# RC_shield.net
KiCad netlist of a schematic drawn in EAGLE
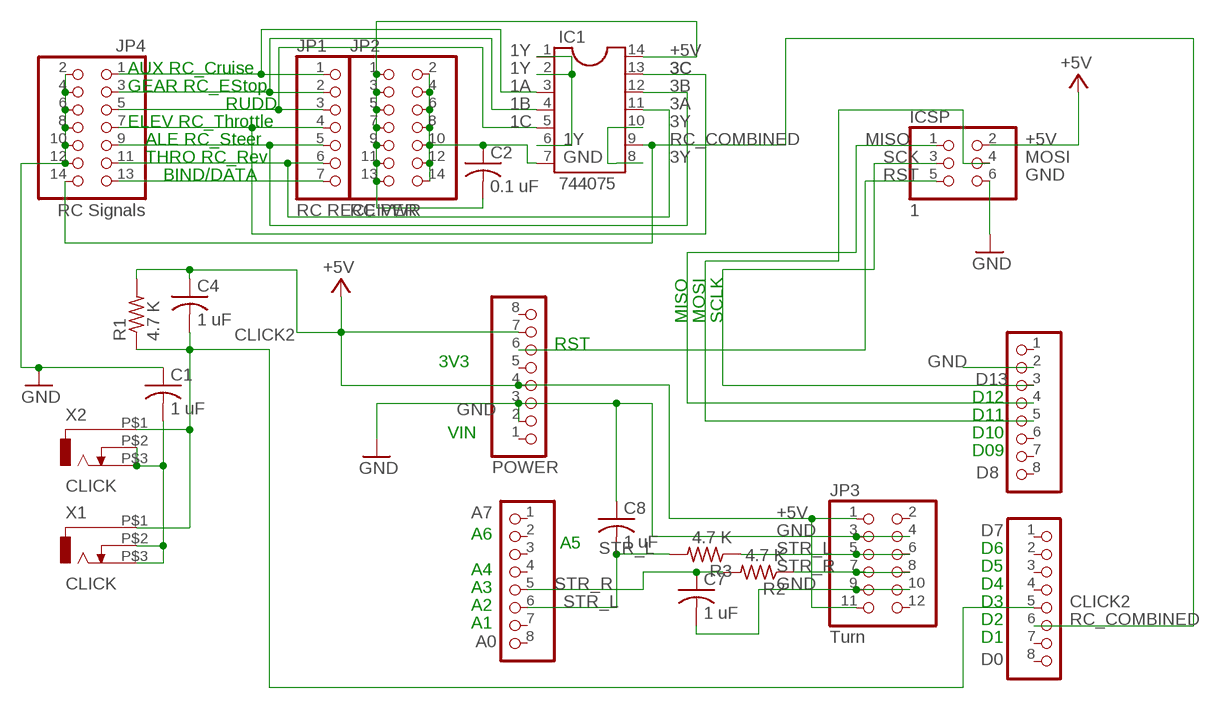
[diagram p0: schematic, sheet 1]

(export (version "E")
  (design (tool "Eeschema 10.0.6"))
  (components
    (comp (ref "A0")
      (value "A7")
      (footprint "eagle-import:1X08")
      (libsource (lib "eagle-import") (part "PINHD-1X8"))
    )
    (comp (ref "C1")
      (value "1 uF")
      (footprint "eagle-import:C025-030X050")
      (libsource (lib "eagle-import") (part "C-US025-030X050"))
    )
    (comp (ref "C2")
      (value "0.1 uF")
      (footprint "eagle-import:C025-030X050")
      (libsource (lib "eagle-import") (part "C-US025-030X050"))
    )
    (comp (ref "C4")
      (value "1 uF")
      (footprint "eagle-import:C025-030X050")
      (libsource (lib "eagle-import") (part "C-US025-030X050"))
    )
    (comp (ref "C7")
      (value "1 uF")
      (footprint "eagle-import:C025-030X050")
      (libsource (lib "eagle-import") (part "C-US025-030X050"))
    )
    (comp (ref "C8")
      (value "1 uF")
      (footprint "eagle-import:C025-030X050")
      (libsource (lib "eagle-import") (part "C-US025-030X050"))
    )
    (comp (ref "D0")
      (value "D7")
      (footprint "eagle-import:1X08")
      (libsource (lib "eagle-import") (part "PINHD-1X8"))
    )
    (comp (ref "D8")
      (value "D13")
      (footprint "eagle-import:1X08")
      (libsource (lib "eagle-import") (part "PINHD-1X8"))
    )
    (comp (ref "IC1")
      (value "744075")
      (footprint "eagle-import:DIL14")
      (libsource (lib "eagle-import") (part "DIL14"))
    )
    (comp (ref "ICSP")
      (value "1")
      (footprint "eagle-import:2X03")
      (libsource (lib "eagle-import") (part "PINHD-2X3"))
    )
    (comp (ref "JP1")
      (value "RC RECEIVER")
      (footprint "eagle-import:1X07")
      (libsource (lib "eagle-import") (part "PINHD-1X7"))
    )
    (comp (ref "JP2")
      (value "RC PWR")
      (footprint "eagle-import:2X07")
      (libsource (lib "eagle-import") (part "PINHD-2X7"))
    )
    (comp (ref "JP3")
      (value "Turn")
      (footprint "eagle-import:2X06")
      (libsource (lib "eagle-import") (part "PINHD-2X6"))
    )
    (comp (ref "JP4")
      (value "RC Signals")
      (footprint "eagle-import:2X07")
      (libsource (lib "eagle-import") (part "PINHD-2X7"))
    )
    (comp (ref "POWER")
      (value "GND")
      (footprint "eagle-import:1X08")
      (libsource (lib "eagle-import") (part "PINHD-1X8"))
    )
    (comp (ref "R1")
      (value "4.7 K")
      (footprint "eagle-import:0207_10")
      (libsource (lib "eagle-import") (part "R-US_0207/10"))
    )
    (comp (ref "R2")
      (value "4.7 K")
      (footprint "eagle-import:0207_10")
      (libsource (lib "eagle-import") (part "R-US_0207/10"))
    )
    (comp (ref "R3")
      (value "4.7 K")
      (footprint "eagle-import:0207_10")
      (libsource (lib "eagle-import") (part "R-US_0207/10"))
    )
    (comp (ref "X1")
      (value "CLICK")
      (footprint "eagle-import:ODO_JACK")
      (libsource (lib "eagle-import") (part "ODO_JACK"))
    )
    (comp (ref "X2")
      (value "CLICK")
      (footprint "eagle-import:ODO_JACK")
      (libsource (lib "eagle-import") (part "ODO_JACK"))
    )
  )
  (nets
    (net (code "1") (name "+5V") (class "Default")
      (node (ref "C2") (pin "2") (pinfunction "2_2") (pintype "passive"))
      (node (ref "C4") (pin "1") (pinfunction "1_1") (pintype "passive"))
      (node (ref "IC1") (pin "14") (pinfunction "14_14") (pintype "passive"))
      (node (ref "ICSP") (pin "2") (pinfunction "2_2") (pintype "passive"))
      (node (ref "JP2") (pin "1") (pinfunction "1_1") (pintype "passive"))
      (node (ref "JP2") (pin "11") (pinfunction "11_11") (pintype "passive"))
      (node (ref "JP2") (pin "13") (pinfunction "13_13") (pintype "passive"))
      (node (ref "JP2") (pin "3") (pinfunction "3_3") (pintype "passive"))
      (node (ref "JP2") (pin "5") (pinfunction "5_5") (pintype "passive"))
      (node (ref "JP2") (pin "7") (pinfunction "7_7") (pintype "passive"))
      (node (ref "JP2") (pin "9") (pinfunction "9_9") (pintype "passive"))
      (node (ref "JP3") (pin "1") (pinfunction "1_1") (pintype "passive"))
      (node (ref "JP3") (pin "11") (pinfunction "11_11") (pintype "passive"))
      (node (ref "POWER") (pin "4") (pinfunction "4_4") (pintype "passive"))
      (node (ref "POWER") (pin "7") (pinfunction "7_7") (pintype "passive"))
      (node (ref "R1") (pin "2") (pinfunction "2_2") (pintype "passive"))
    )
    (net (code "2") (name "/1A") (class "Default")
      (node (ref "IC1") (pin "3") (pinfunction "3_3") (pintype "passive"))
      (node (ref "JP1") (pin "1") (pinfunction "1_1") (pintype "passive"))
      (node (ref "JP4") (pin "1") (pinfunction "1_1") (pintype "passive"))
    )
    (net (code "3") (name "/1B") (class "Default")
      (node (ref "IC1") (pin "4") (pinfunction "4_4") (pintype "passive"))
      (node (ref "JP1") (pin "2") (pinfunction "2_2") (pintype "passive"))
      (node (ref "JP4") (pin "3") (pinfunction "3_3") (pintype "passive"))
    )
    (net (code "4") (name "/1C") (class "Default")
      (node (ref "IC1") (pin "5") (pinfunction "5_5") (pintype "passive"))
      (node (ref "JP1") (pin "3") (pinfunction "3_3") (pintype "passive"))
      (node (ref "JP4") (pin "5") (pinfunction "5_5") (pintype "passive"))
    )
    (net (code "5") (name "/1Y") (class "Default")
      (node (ref "IC1") (pin "1") (pinfunction "1_1") (pintype "passive"))
      (node (ref "IC1") (pin "2") (pinfunction "2_2") (pintype "passive"))
      (node (ref "IC1") (pin "6") (pinfunction "6_6") (pintype "passive"))
    )
    (net (code "6") (name "/3A") (class "Default")
      (node (ref "IC1") (pin "11") (pinfunction "11_11") (pintype "passive"))
      (node (ref "JP1") (pin "6") (pinfunction "6_6") (pintype "passive"))
      (node (ref "JP4") (pin "11") (pinfunction "11_11") (pintype "passive"))
    )
    (net (code "7") (name "/3B") (class "Default")
      (node (ref "IC1") (pin "12") (pinfunction "12_12") (pintype "passive"))
      (node (ref "JP1") (pin "5") (pinfunction "5_5") (pintype "passive"))
      (node (ref "JP4") (pin "9") (pinfunction "9_9") (pintype "passive"))
    )
    (net (code "8") (name "/3C") (class "Default")
      (node (ref "IC1") (pin "13") (pinfunction "13_13") (pintype "passive"))
      (node (ref "JP1") (pin "4") (pinfunction "4_4") (pintype "passive"))
      (node (ref "JP4") (pin "7") (pinfunction "7_7") (pintype "passive"))
    )
    (net (code "9") (name "/3Y") (class "Default")
      (node (ref "IC1") (pin "10") (pinfunction "10_10") (pintype "passive"))
      (node (ref "IC1") (pin "8") (pinfunction "8_8") (pintype "passive"))
    )
    (net (code "10") (name "/CLICK2") (class "Default")
      (node (ref "C4") (pin "2") (pinfunction "2_2") (pintype "passive"))
      (node (ref "D0") (pin "5") (pinfunction "5_5") (pintype "passive"))
      (node (ref "R1") (pin "1") (pinfunction "1_1") (pintype "passive"))
      (node (ref "X1") (pin "P$1") (pinfunction "1_P$1") (pintype "passive"))
      (node (ref "X2") (pin "P$1") (pinfunction "1_P$1") (pintype "passive"))
    )
    (net (code "11") (name "/MISO") (class "Default")
      (node (ref "D8") (pin "4") (pinfunction "4_4") (pintype "passive"))
      (node (ref "ICSP") (pin "1") (pinfunction "1_1") (pintype "passive"))
    )
    (net (code "12") (name "/MOSI") (class "Default")
      (node (ref "D8") (pin "5") (pinfunction "5_5") (pintype "passive"))
      (node (ref "ICSP") (pin "4") (pinfunction "4_4") (pintype "passive"))
    )
    (net (code "13") (name "/RC_COMBINED") (class "Default")
      (node (ref "D0") (pin "6") (pinfunction "6_6") (pintype "passive"))
      (node (ref "IC1") (pin "9") (pinfunction "9_9") (pintype "passive"))
      (node (ref "JP4") (pin "14") (pinfunction "14_14") (pintype "passive"))
    )
    (net (code "14") (name "/RST") (class "Default")
      (node (ref "ICSP") (pin "5") (pinfunction "5_5") (pintype "passive"))
      (node (ref "POWER") (pin "6") (pinfunction "6_6") (pintype "passive"))
    )
    (net (code "15") (name "/SCK") (class "Default")
      (node (ref "D8") (pin "3") (pinfunction "3_3") (pintype "passive"))
      (node (ref "ICSP") (pin "3") (pinfunction "3_3") (pintype "passive"))
    )
    (net (code "16") (name "/STR_L") (class "Default")
      (node (ref "A0") (pin "6") (pinfunction "6_6") (pintype "passive"))
      (node (ref "C8") (pin "2") (pinfunction "2_2") (pintype "passive"))
      (node (ref "R3") (pin "2") (pinfunction "2_2") (pintype "passive"))
    )
    (net (code "17") (name "/STR_R") (class "Default")
      (node (ref "A0") (pin "5") (pinfunction "5_5") (pintype "passive"))
      (node (ref "C7") (pin "1") (pinfunction "1_1") (pintype "passive"))
      (node (ref "R2") (pin "2") (pinfunction "2_2") (pintype "passive"))
    )
    (net (code "18") (name "GND") (class "Default")
      (node (ref "C1") (pin "1") (pinfunction "1_1") (pintype "passive"))
      (node (ref "C2") (pin "1") (pinfunction "1_1") (pintype "passive"))
      (node (ref "C7") (pin "2") (pinfunction "2_2") (pintype "passive"))
      (node (ref "C8") (pin "1") (pinfunction "1_1") (pintype "passive"))
      (node (ref "D8") (pin "2") (pinfunction "2_2") (pintype "passive"))
      (node (ref "IC1") (pin "7") (pinfunction "7_7") (pintype "passive"))
      (node (ref "ICSP") (pin "6") (pinfunction "6_6") (pintype "passive"))
      (node (ref "JP2") (pin "10") (pinfunction "10_10") (pintype "passive"))
      (node (ref "JP2") (pin "12") (pinfunction "12_12") (pintype "passive"))
      (node (ref "JP2") (pin "14") (pinfunction "14_14") (pintype "passive"))
      (node (ref "JP2") (pin "2") (pinfunction "2_2") (pintype "passive"))
      (node (ref "JP2") (pin "4") (pinfunction "4_4") (pintype "passive"))
      (node (ref "JP2") (pin "6") (pinfunction "6_6") (pintype "passive"))
      (node (ref "JP2") (pin "8") (pinfunction "8_8") (pintype "passive"))
      (node (ref "JP3") (pin "10") (pinfunction "10_10") (pintype "passive"))
      (node (ref "JP3") (pin "3") (pinfunction "3_3") (pintype "passive"))
      (node (ref "JP3") (pin "4") (pinfunction "4_4") (pintype "passive"))
      (node (ref "JP3") (pin "9") (pinfunction "9_9") (pintype "passive"))
      (node (ref "JP4") (pin "10") (pinfunction "10_10") (pintype "passive"))
      (node (ref "JP4") (pin "12") (pinfunction "12_12") (pintype "passive"))
      (node (ref "JP4") (pin "2") (pinfunction "2_2") (pintype "passive"))
      (node (ref "JP4") (pin "4") (pinfunction "4_4") (pintype "passive"))
      (node (ref "JP4") (pin "6") (pinfunction "6_6") (pintype "passive"))
      (node (ref "JP4") (pin "8") (pinfunction "8_8") (pintype "passive"))
      (node (ref "POWER") (pin "2") (pinfunction "2_2") (pintype "passive"))
      (node (ref "POWER") (pin "3") (pinfunction "3_3") (pintype "passive"))
    )
    (net (code "19") (name "Net-(JP1-Pad7)") (class "Default")
      (node (ref "JP1") (pin "7") (pinfunction "7_7") (pintype "passive"))
      (node (ref "JP4") (pin "13") (pinfunction "13_13") (pintype "passive"))
    )
    (net (code "20") (name "Net-(JP3-Pad5)") (class "Default")
      (node (ref "JP3") (pin "5") (pinfunction "5_5") (pintype "passive"))
      (node (ref "JP3") (pin "6") (pinfunction "6_6") (pintype "passive"))
      (node (ref "R3") (pin "1") (pinfunction "1_1") (pintype "passive"))
    )
    (net (code "21") (name "Net-(JP3-Pad7)") (class "Default")
      (node (ref "JP3") (pin "7") (pinfunction "7_7") (pintype "passive"))
      (node (ref "JP3") (pin "8") (pinfunction "8_8") (pintype "passive"))
      (node (ref "R2") (pin "1") (pinfunction "1_1") (pintype "passive"))
    )
    (net (code "22") (name "Net-(X1-2)") (class "Default")
      (node (ref "C1") (pin "2") (pinfunction "2_2") (pintype "passive"))
      (node (ref "X1") (pin "P$2") (pinfunction "2_P$2") (pintype "passive"))
      (node (ref "X1") (pin "P$3") (pinfunction "3_P$3") (pintype "passive"))
      (node (ref "X2") (pin "P$2") (pinfunction "2_P$2") (pintype "passive"))
      (node (ref "X2") (pin "P$3") (pinfunction "3_P$3") (pintype "passive"))
    )
    (net (code "23") (name "unconnected-(A0-Pad1)") (class "Default")
      (node (ref "A0") (pin "1") (pinfunction "1_1") (pintype "passive"))
    )
    (net (code "24") (name "unconnected-(A0-Pad2)") (class "Default")
      (node (ref "A0") (pin "2") (pinfunction "2_2") (pintype "passive"))
    )
    (net (code "25") (name "unconnected-(A0-Pad3)") (class "Default")
      (node (ref "A0") (pin "3") (pinfunction "3_3") (pintype "passive"))
    )
    (net (code "26") (name "unconnected-(A0-Pad4)") (class "Default")
      (node (ref "A0") (pin "4") (pinfunction "4_4") (pintype "passive"))
    )
    (net (code "27") (name "unconnected-(A0-Pad7)") (class "Default")
      (node (ref "A0") (pin "7") (pinfunction "7_7") (pintype "passive"))
    )
    (net (code "28") (name "unconnected-(A0-Pad8)") (class "Default")
      (node (ref "A0") (pin "8") (pinfunction "8_8") (pintype "passive"))
    )
    (net (code "29") (name "unconnected-(D0-Pad1)") (class "Default")
      (node (ref "D0") (pin "1") (pinfunction "1_1") (pintype "passive"))
    )
    (net (code "30") (name "unconnected-(D0-Pad2)") (class "Default")
      (node (ref "D0") (pin "2") (pinfunction "2_2") (pintype "passive"))
    )
    (net (code "31") (name "unconnected-(D0-Pad3)") (class "Default")
      (node (ref "D0") (pin "3") (pinfunction "3_3") (pintype "passive"))
    )
    (net (code "32") (name "unconnected-(D0-Pad4)") (class "Default")
      (node (ref "D0") (pin "4") (pinfunction "4_4") (pintype "passive"))
    )
    (net (code "33") (name "unconnected-(D0-Pad7)") (class "Default")
      (node (ref "D0") (pin "7") (pinfunction "7_7") (pintype "passive"))
    )
    (net (code "34") (name "unconnected-(D0-Pad8)") (class "Default")
      (node (ref "D0") (pin "8") (pinfunction "8_8") (pintype "passive"))
    )
    (net (code "35") (name "unconnected-(D8-Pad1)") (class "Default")
      (node (ref "D8") (pin "1") (pinfunction "1_1") (pintype "passive"))
    )
    (net (code "36") (name "unconnected-(D8-Pad6)") (class "Default")
      (node (ref "D8") (pin "6") (pinfunction "6_6") (pintype "passive"))
    )
    (net (code "37") (name "unconnected-(D8-Pad7)") (class "Default")
      (node (ref "D8") (pin "7") (pinfunction "7_7") (pintype "passive"))
    )
    (net (code "38") (name "unconnected-(D8-Pad8)") (class "Default")
      (node (ref "D8") (pin "8") (pinfunction "8_8") (pintype "passive"))
    )
    (net (code "39") (name "unconnected-(JP3-Pad2)") (class "Default")
      (node (ref "JP3") (pin "2") (pinfunction "2_2") (pintype "passive"))
    )
    (net (code "40") (name "unconnected-(JP3-Pad12)") (class "Default")
      (node (ref "JP3") (pin "12") (pinfunction "12_12") (pintype "passive"))
    )
    (net (code "41") (name "unconnected-(POWER-Pad1)") (class "Default")
      (node (ref "POWER") (pin "1") (pinfunction "1_1") (pintype "passive"))
    )
    (net (code "42") (name "unconnected-(POWER-Pad5)") (class "Default")
      (node (ref "POWER") (pin "5") (pinfunction "5_5") (pintype "passive"))
    )
    (net (code "43") (name "unconnected-(POWER-Pad8)") (class "Default")
      (node (ref "POWER") (pin "8") (pinfunction "8_8") (pintype "passive"))
    )
  )
)
